# AltiumSTM32_Schematic.net
KiCad netlist of a schematic drawn in Altium Designer
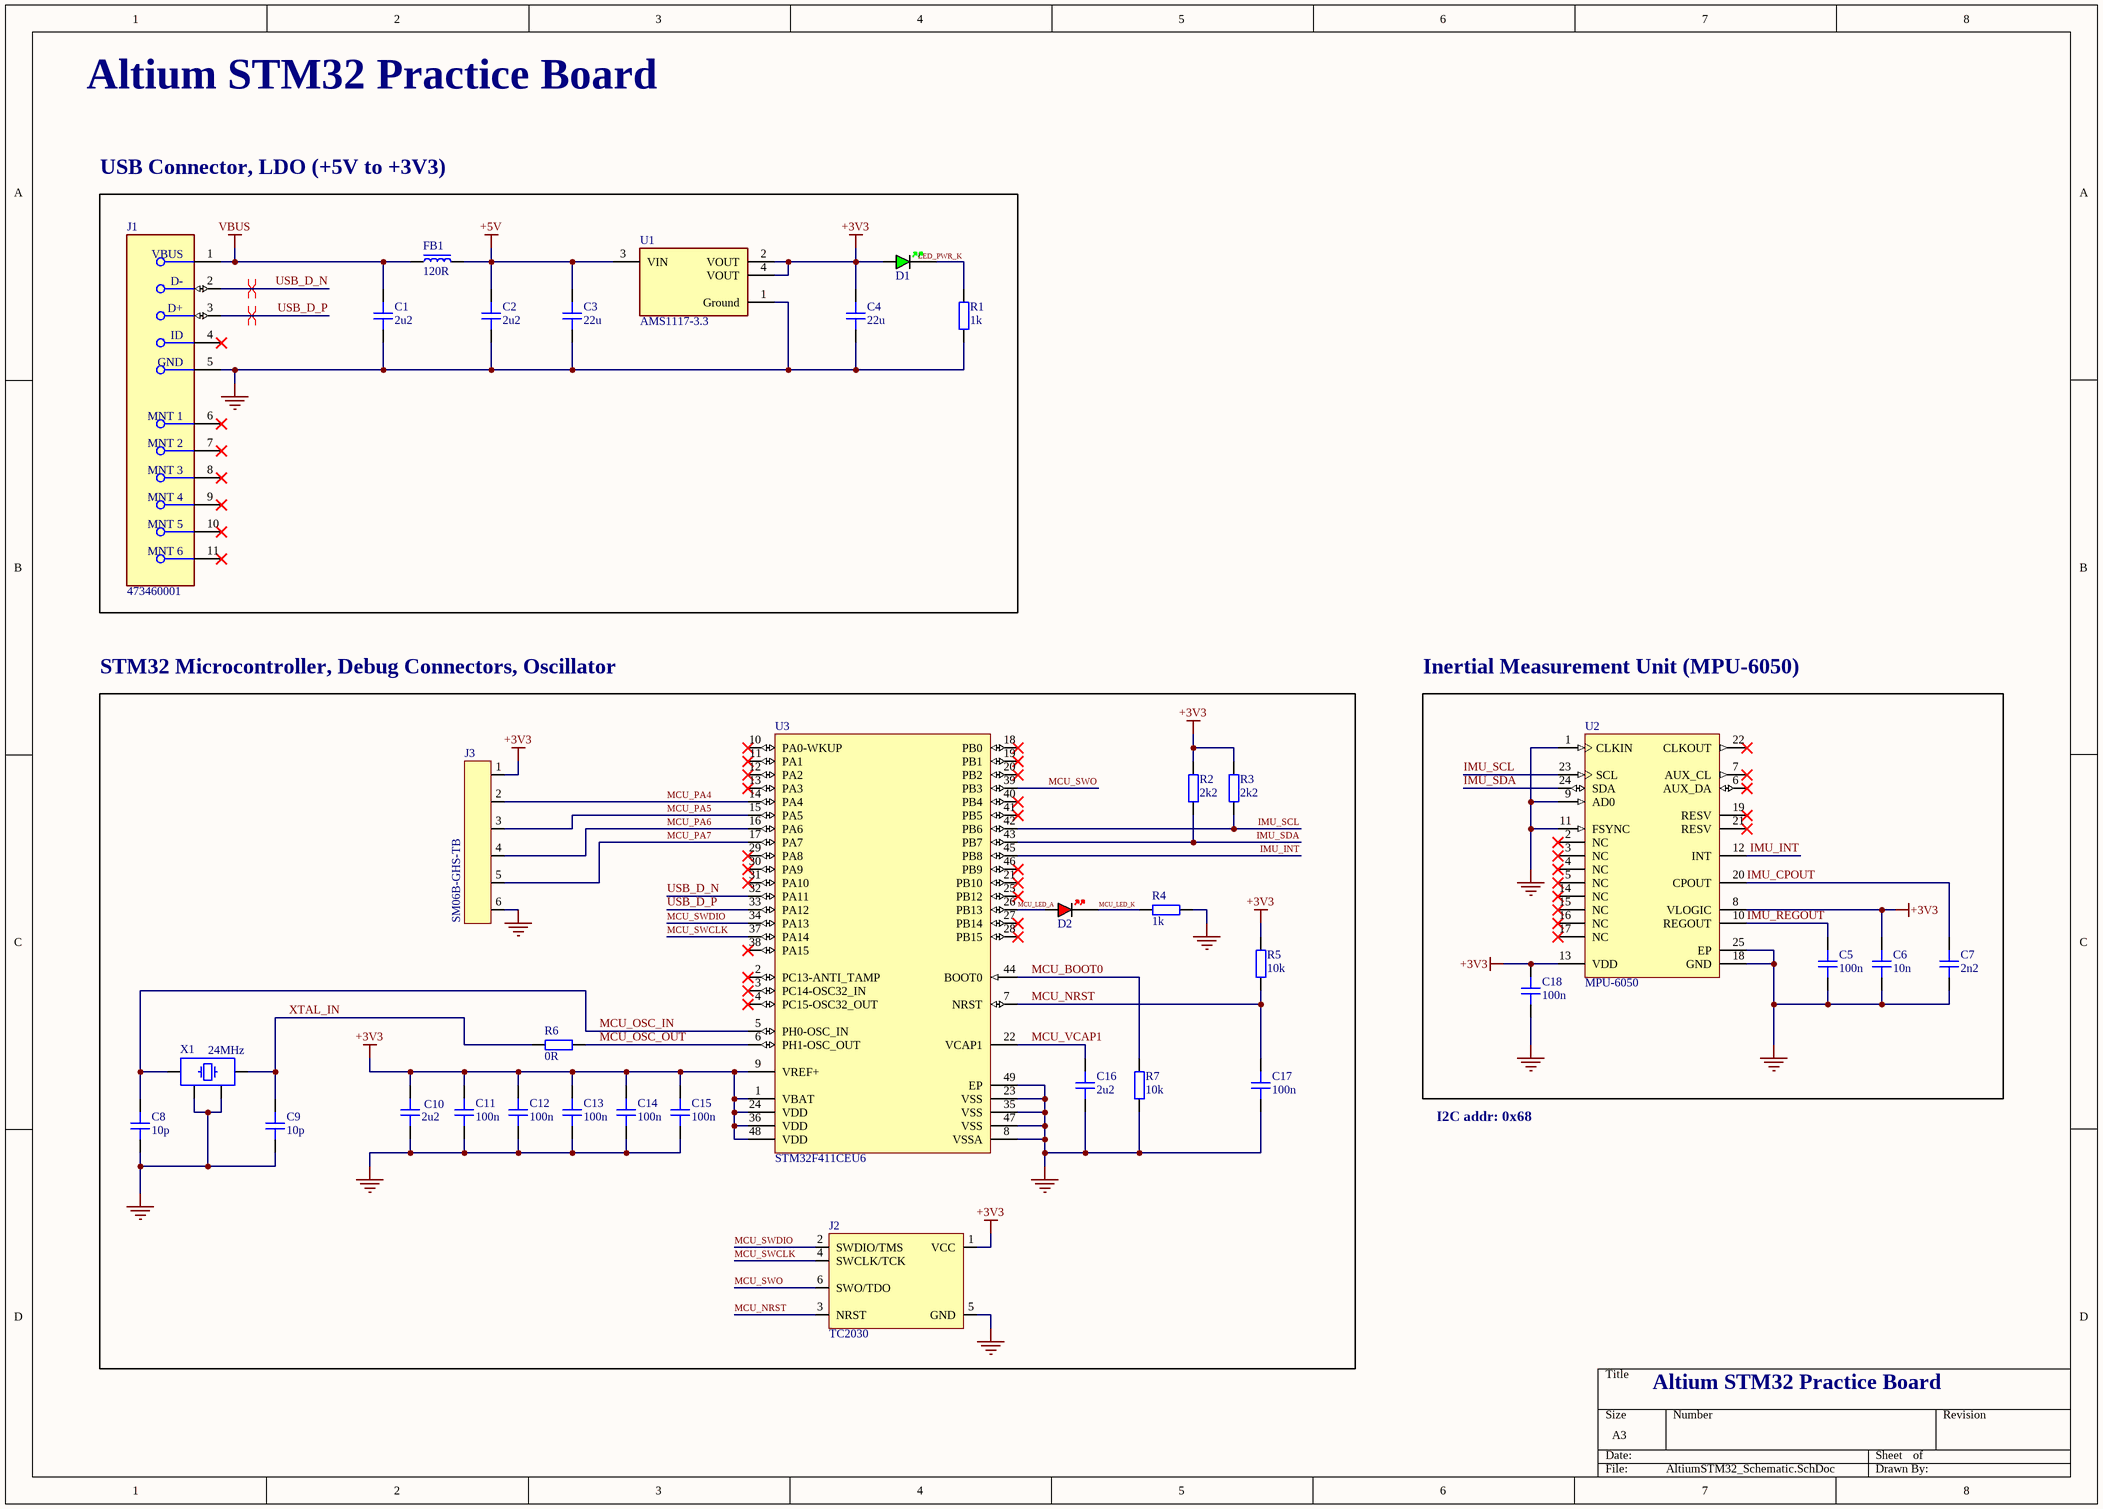
[diagram p0: AltiumSTM32_Schematic.SchDoc]

(export (version "E")
  (design (tool "Eeschema 10.0.6"))
  (components
    (comp (ref "C1")
      (value "2u2")
      (footprint "CAP_0603")
      (description "Capacitor SMD 0603")
      (libsource (lib "Schematic-Lib-PhilsLab") (part "CAP_0603"))
    )
    (comp (ref "C2")
      (value "2u2")
      (footprint "CAP_0603")
      (description "Capacitor SMD 0603")
      (libsource (lib "Schematic-Lib-PhilsLab") (part "CAP_0603"))
    )
    (comp (ref "C3")
      (value "22u")
      (footprint "CAP_0805")
      (description "Capacitor SMD 0805")
      (libsource (lib "Schematic-Lib-PhilsLab") (part "CAP_0805"))
    )
    (comp (ref "C4")
      (value "22u")
      (footprint "CAP_0805")
      (description "Capacitor SMD 0805")
      (libsource (lib "Schematic-Lib-PhilsLab") (part "CAP_0805"))
    )
    (comp (ref "C5")
      (value "100n")
      (footprint "CAP_0402")
      (description "Capacitor SMD 0402")
      (libsource (lib "Schematic-Lib-PhilsLab") (part "CAP_0402"))
    )
    (comp (ref "C6")
      (value "10n")
      (footprint "CAP_0402")
      (description "Capacitor SMD 0402")
      (libsource (lib "Schematic-Lib-PhilsLab") (part "CAP_0402"))
    )
    (comp (ref "C7")
      (value "2n2")
      (footprint "CAP_0402")
      (description "Capacitor SMD 0402")
      (libsource (lib "Schematic-Lib-PhilsLab") (part "CAP_0402"))
    )
    (comp (ref "C8")
      (value "10p")
      (footprint "CAP_0402")
      (description "Capacitor SMD 0402")
      (libsource (lib "Schematic-Lib-PhilsLab") (part "CAP_0402"))
    )
    (comp (ref "C9")
      (value "10p")
      (footprint "CAP_0402")
      (description "Capacitor SMD 0402")
      (libsource (lib "Schematic-Lib-PhilsLab") (part "CAP_0402"))
    )
    (comp (ref "C10")
      (value "2u2")
      (footprint "CAP_0603")
      (description "Capacitor SMD 0603")
      (libsource (lib "Schematic-Lib-PhilsLab") (part "CAP_0603"))
    )
    (comp (ref "C11")
      (value "100n")
      (footprint "CAP_0402")
      (description "Capacitor SMD 0402")
      (libsource (lib "Schematic-Lib-PhilsLab") (part "CAP_0402"))
    )
    (comp (ref "C12")
      (value "100n")
      (footprint "CAP_0402")
      (description "Capacitor SMD 0402")
      (libsource (lib "Schematic-Lib-PhilsLab") (part "CAP_0402"))
    )
    (comp (ref "C13")
      (value "100n")
      (footprint "CAP_0402")
      (description "Capacitor SMD 0402")
      (libsource (lib "Schematic-Lib-PhilsLab") (part "CAP_0402"))
    )
    (comp (ref "C14")
      (value "100n")
      (footprint "CAP_0402")
      (description "Capacitor SMD 0402")
      (libsource (lib "Schematic-Lib-PhilsLab") (part "CAP_0402"))
    )
    (comp (ref "C15")
      (value "100n")
      (footprint "CAP_0402")
      (description "Capacitor SMD 0402")
      (libsource (lib "Schematic-Lib-PhilsLab") (part "CAP_0402"))
    )
    (comp (ref "C16")
      (value "2u2")
      (footprint "CAP_0603")
      (description "Capacitor SMD 0603")
      (libsource (lib "Schematic-Lib-PhilsLab") (part "CAP_0603"))
    )
    (comp (ref "C17")
      (value "100n")
      (footprint "CAP_0402")
      (description "Capacitor SMD 0402")
      (libsource (lib "Schematic-Lib-PhilsLab") (part "CAP_0402"))
    )
    (comp (ref "C18")
      (value "100n")
      (footprint "CAP_0402")
      (description "Capacitor SMD 0402")
      (libsource (lib "Schematic-Lib-PhilsLab") (part "CAP_0402"))
    )
    (comp (ref "D1")
      (value "GREEN")
      (footprint "LED_0402_GREEN")
      (description "LED 0402 GREEN SMD")
      (libsource (lib "Schematic-Lib-PhilsLab") (part "LED_0402_GREEN"))
    )
    (comp (ref "D2")
      (value "RED")
      (footprint "LED_0402_RED")
      (description "LED 0402 RED SMD")
      (libsource (lib "Schematic-Lib-PhilsLab") (part "LED_0402_RED"))
    )
    (comp (ref "FB1")
      (value "120R")
      (footprint "FB_0603")
      (description "Ferrite Bead SMD 0603")
      (libsource (lib "Schematic-Lib-PhilsLab") (part "FB_0603"))
    )
    (comp (ref "J1")
      (value "473460001")
      (footprint "FP-473460001-MFG")
      (description "CONN RCPT USB2.0 MICRO B SMD R/A")
      (fields
        (field (name "OCTOPART") "https://octopart.com/47346-0001-molex-7164928")
        (field (name "MANUFACTURER") "Molex")
      )
      (libsource (lib "Altium Content Vault") (part "53ae1f1d9b557310b43ca686e5bb76a"))
    )
    (comp (ref "J2")
      (value "TC2030")
      (footprint "TC2030-FP")
      (description "Tag-Connect No-Solder SWD Debug Connector DO NOT PLACE")
      (fields (field (name "MANUFACTURER") "Tag-Connect"))
      (libsource (lib "Schematic-Lib-PhilsLab") (part "TC2030"))
    )
    (comp (ref "J3")
      (value "SM06B-GHS-TB")
      (footprint "SM06B-GHS-TB")
      (description "Header Connector 6 Position 1.25MM Pitch SMD Horizontal JST GH")
      (fields (field (name "MANUFACTURER") "JST"))
      (libsource (lib "Schematic-Lib-PhilsLab") (part "SM06B-GHS-TB"))
    )
    (comp (ref "R1")
      (value "1k")
      (footprint "RES_0402")
      (description "Resistor SMD 0402")
      (libsource (lib "Schematic-Lib-PhilsLab") (part "RES_0402"))
    )
    (comp (ref "R2")
      (value "2k2")
      (footprint "RES_0402")
      (description "Resistor SMD 0402")
      (libsource (lib "Schematic-Lib-PhilsLab") (part "RES_0402"))
    )
    (comp (ref "R3")
      (value "2k2")
      (footprint "RES_0402")
      (description "Resistor SMD 0402")
      (libsource (lib "Schematic-Lib-PhilsLab") (part "RES_0402"))
    )
    (comp (ref "R4")
      (value "1k")
      (footprint "RES_0402")
      (description "Resistor SMD 0402")
      (libsource (lib "Schematic-Lib-PhilsLab") (part "RES_0402"))
    )
    (comp (ref "R5")
      (value "10k")
      (footprint "RES_0402")
      (description "Resistor SMD 0402")
      (libsource (lib "Schematic-Lib-PhilsLab") (part "RES_0402"))
    )
    (comp (ref "R6")
      (value "0R")
      (footprint "RES_0402")
      (description "Resistor SMD 0402")
      (libsource (lib "Schematic-Lib-PhilsLab") (part "RES_0402"))
    )
    (comp (ref "R7")
      (value "10k")
      (footprint "RES_0402")
      (description "Resistor SMD 0402")
      (libsource (lib "Schematic-Lib-PhilsLab") (part "RES_0402"))
    )
    (comp (ref "U1")
      (value "AMS1117-3.3")
      (footprint "FP-AMS1117-IPC_C")
      (description "LDO Voltage Regulators 1A, 3.3V")
      (fields
        (field (name "OCTOPART") "https://octopart.com/ams1117-3.3-advanced+monolithic+systems-25899300")
        (field (name "MANUFACTURER") "Advanced Monolithic Systems")
      )
      (libsource (lib "Altium Content Vault") (part "8bdbb5f8e77002000e30dd2845d0354"))
    )
    (comp (ref "U2")
      (value "MPU-6050")
      (footprint "IS-QFN-24_V")
      (fields (field (name "MANUFACTURER") "InvenSense"))
      (libsource (lib "Altium Content Vault") (part "IS-MPU-6050-QFN-24"))
    )
    (comp (ref "U3")
      (value "STM32F411CEU6")
      (footprint "STM-UFQFPN48_L")
      (libsource (lib "Altium Content Vault") (part "MC-ARM-STM32F411-UFQFPN48"))
    )
    (comp (ref "X1")
      (value "24MHz")
      (footprint "XTAL_3225")
      (description "Crystal SMD 24MHz 10PPM 7pF 3225")
      (fields
        (field (name "MANUFACTURER") "Epson")
        (field (name "MANUFACTURER PART NUMBER") "TSX-3225 24.0000MF15X-AC")
      )
      (libsource (lib "Schematic-Lib-PhilsLab") (part "TSX-3225_24.0000MF15X-AC"))
    )
  )
  (nets
    (net (code "1") (name "+3V3") (class "Default")
      (node (ref "C10") (pin "2") (pinfunction "2_2") (pintype "passive"))
      (node (ref "C11") (pin "2") (pinfunction "2_2") (pintype "passive"))
      (node (ref "C12") (pin "2") (pinfunction "2_2") (pintype "passive"))
      (node (ref "C13") (pin "2") (pinfunction "2_2") (pintype "passive"))
      (node (ref "C14") (pin "2") (pinfunction "2_2") (pintype "passive"))
      (node (ref "C15") (pin "2") (pinfunction "2_2") (pintype "passive"))
      (node (ref "C18") (pin "1") (pinfunction "1_1") (pintype "passive"))
      (node (ref "C4") (pin "2") (pinfunction "2_2") (pintype "passive"))
      (node (ref "C6") (pin "1") (pinfunction "1_1") (pintype "passive"))
      (node (ref "D1") (pin "A") (pinfunction "A_A") (pintype "passive"))
      (node (ref "J2") (pin "1") (pinfunction "VCC_1") (pintype "passive"))
      (node (ref "J3") (pin "1") (pinfunction "1_1") (pintype "passive"))
      (node (ref "R2") (pin "2") (pinfunction "2_2") (pintype "passive"))
      (node (ref "R3") (pin "2") (pinfunction "2_2") (pintype "passive"))
      (node (ref "R5") (pin "2") (pinfunction "2_2") (pintype "passive"))
      (node (ref "U1") (pin "2") (pinfunction "VOUT_2") (pintype "passive"))
      (node (ref "U1") (pin "4") (pinfunction "VOUT_4") (pintype "passive"))
      (node (ref "U2") (pin "13") (pinfunction "VDD_13") (pintype "power_in"))
      (node (ref "U2") (pin "8") (pinfunction "VLOGIC_8") (pintype "power_in"))
      (node (ref "U3") (pin "1") (pinfunction "VBAT_1") (pintype "power_in"))
      (node (ref "U3") (pin "24") (pinfunction "VDD_24") (pintype "power_in"))
      (node (ref "U3") (pin "36") (pinfunction "VDD_36") (pintype "power_in"))
      (node (ref "U3") (pin "48") (pinfunction "VDD_48") (pintype "power_in"))
      (node (ref "U3") (pin "9") (pinfunction "VREF+_9") (pintype "power_in"))
    )
    (net (code "2") (name "+5V") (class "Default")
      (node (ref "C2") (pin "2") (pinfunction "2_2") (pintype "passive"))
      (node (ref "C3") (pin "2") (pinfunction "2_2") (pintype "passive"))
      (node (ref "FB1") (pin "2") (pinfunction "2_2") (pintype "passive"))
      (node (ref "U1") (pin "3") (pinfunction "VIN_3") (pintype "power_in"))
    )
    (net (code "3") (name "/IMU_CPOUT") (class "Default")
      (node (ref "C7") (pin "1") (pinfunction "1_1") (pintype "passive"))
      (node (ref "U2") (pin "20") (pinfunction "CPOUT_20") (pintype "passive"))
    )
    (net (code "4") (name "/IMU_INT") (class "Default")
      (node (ref "U2") (pin "12") (pinfunction "INT_12") (pintype "open_collector"))
      (node (ref "U3") (pin "45") (pinfunction "PB8_45") (pintype "bidirectional"))
    )
    (net (code "5") (name "/IMU_REGOUT") (class "Default")
      (node (ref "C5") (pin "1") (pinfunction "1_1") (pintype "passive"))
      (node (ref "U2") (pin "10") (pinfunction "REGOUT_10") (pintype "passive"))
    )
    (net (code "6") (name "/IMU_SCL") (class "Default")
      (node (ref "R3") (pin "1") (pinfunction "1_1") (pintype "passive"))
      (node (ref "U2") (pin "23") (pinfunction "SCL_23") (pintype "input"))
      (node (ref "U3") (pin "42") (pinfunction "PB6_42") (pintype "bidirectional"))
    )
    (net (code "7") (name "/IMU_SDA") (class "Default")
      (node (ref "R2") (pin "1") (pinfunction "1_1") (pintype "passive"))
      (node (ref "U2") (pin "24") (pinfunction "SDA_24") (pintype "bidirectional"))
      (node (ref "U3") (pin "43") (pinfunction "PB7_43") (pintype "bidirectional"))
    )
    (net (code "8") (name "/LED_PWR_K") (class "Default")
      (node (ref "D1") (pin "K") (pinfunction "K_K") (pintype "passive"))
      (node (ref "R1") (pin "2") (pinfunction "2_2") (pintype "passive"))
    )
    (net (code "9") (name "/MCU_BOOT0") (class "Default")
      (node (ref "R7") (pin "2") (pinfunction "2_2") (pintype "passive"))
      (node (ref "U3") (pin "44") (pinfunction "BOOT0_44") (pintype "input"))
    )
    (net (code "10") (name "/MCU_LED_A") (class "Default")
      (node (ref "D2") (pin "A") (pinfunction "A_A") (pintype "passive"))
      (node (ref "U3") (pin "26") (pinfunction "PB13_26") (pintype "bidirectional"))
    )
    (net (code "11") (name "/MCU_LED_K") (class "Default")
      (node (ref "D2") (pin "K") (pinfunction "K_K") (pintype "passive"))
      (node (ref "R4") (pin "2") (pinfunction "2_2") (pintype "passive"))
    )
    (net (code "12") (name "/MCU_NRST") (class "Default")
      (node (ref "C17") (pin "2") (pinfunction "2_2") (pintype "passive"))
      (node (ref "J2") (pin "3") (pinfunction "NRST_3") (pintype "passive"))
      (node (ref "R5") (pin "1") (pinfunction "1_1") (pintype "passive"))
      (node (ref "U3") (pin "7") (pinfunction "NRST_7") (pintype "bidirectional"))
    )
    (net (code "13") (name "/MCU_OSC_IN") (class "Default")
      (node (ref "C8") (pin "2") (pinfunction "2_2") (pintype "passive"))
      (node (ref "U3") (pin "5") (pinfunction "PH0-OSC_IN_5") (pintype "bidirectional"))
      (node (ref "X1") (pin "1") (pinfunction "1_1") (pintype "passive"))
    )
    (net (code "14") (name "/MCU_OSC_OUT") (class "Default")
      (node (ref "R6") (pin "2") (pinfunction "2_2") (pintype "passive"))
      (node (ref "U3") (pin "6") (pinfunction "PH1-OSC_OUT_6") (pintype "bidirectional"))
    )
    (net (code "15") (name "/MCU_PA4") (class "Default")
      (node (ref "J3") (pin "2") (pinfunction "2_2") (pintype "passive"))
      (node (ref "U3") (pin "14") (pinfunction "PA4_14") (pintype "bidirectional"))
    )
    (net (code "16") (name "/MCU_PA5") (class "Default")
      (node (ref "J3") (pin "3") (pinfunction "3_3") (pintype "passive"))
      (node (ref "U3") (pin "15") (pinfunction "PA5_15") (pintype "bidirectional"))
    )
    (net (code "17") (name "/MCU_PA6") (class "Default")
      (node (ref "J3") (pin "4") (pinfunction "4_4") (pintype "passive"))
      (node (ref "U3") (pin "16") (pinfunction "PA6_16") (pintype "bidirectional"))
    )
    (net (code "18") (name "/MCU_PA7") (class "Default")
      (node (ref "J3") (pin "5") (pinfunction "5_5") (pintype "passive"))
      (node (ref "U3") (pin "17") (pinfunction "PA7_17") (pintype "bidirectional"))
    )
    (net (code "19") (name "/MCU_SWCLK") (class "Default")
      (node (ref "J2") (pin "4") (pinfunction "SWCLK/TCK_4") (pintype "passive"))
      (node (ref "U3") (pin "37") (pinfunction "PA14_37") (pintype "bidirectional"))
    )
    (net (code "20") (name "/MCU_SWDIO") (class "Default")
      (node (ref "J2") (pin "2") (pinfunction "SWDIO/TMS_2") (pintype "passive"))
      (node (ref "U3") (pin "34") (pinfunction "PA13_34") (pintype "bidirectional"))
    )
    (net (code "21") (name "/MCU_SWO") (class "Default")
      (node (ref "J2") (pin "6") (pinfunction "SWO/TDO_6") (pintype "passive"))
      (node (ref "U3") (pin "39") (pinfunction "PB3_39") (pintype "bidirectional"))
    )
    (net (code "22") (name "/MCU_VCAP1") (class "Default")
      (node (ref "C16") (pin "2") (pinfunction "2_2") (pintype "passive"))
      (node (ref "U3") (pin "22") (pinfunction "VCAP1_22") (pintype "passive"))
    )
    (net (code "23") (name "/USB_D_N") (class "Default")
      (node (ref "J1") (pin "2") (pinfunction "D-_2") (pintype "bidirectional"))
      (node (ref "U3") (pin "32") (pinfunction "PA11_32") (pintype "bidirectional"))
    )
    (net (code "24") (name "/USB_D_P") (class "Default")
      (node (ref "J1") (pin "3") (pinfunction "D+_3") (pintype "bidirectional"))
      (node (ref "U3") (pin "33") (pinfunction "PA12_33") (pintype "bidirectional"))
    )
    (net (code "25") (name "/XTAL_IN") (class "Default")
      (node (ref "C9") (pin "2") (pinfunction "2_2") (pintype "passive"))
      (node (ref "R6") (pin "1") (pinfunction "1_1") (pintype "passive"))
      (node (ref "X1") (pin "3") (pinfunction "3_3") (pintype "passive"))
    )
    (net (code "26") (name "GND") (class "Default")
      (node (ref "C1") (pin "1") (pinfunction "1_1") (pintype "passive"))
      (node (ref "C10") (pin "1") (pinfunction "1_1") (pintype "passive"))
      (node (ref "C11") (pin "1") (pinfunction "1_1") (pintype "passive"))
      (node (ref "C12") (pin "1") (pinfunction "1_1") (pintype "passive"))
      (node (ref "C13") (pin "1") (pinfunction "1_1") (pintype "passive"))
      (node (ref "C14") (pin "1") (pinfunction "1_1") (pintype "passive"))
      (node (ref "C15") (pin "1") (pinfunction "1_1") (pintype "passive"))
      (node (ref "C16") (pin "1") (pinfunction "1_1") (pintype "passive"))
      (node (ref "C17") (pin "1") (pinfunction "1_1") (pintype "passive"))
      (node (ref "C18") (pin "2") (pinfunction "2_2") (pintype "passive"))
      (node (ref "C2") (pin "1") (pinfunction "1_1") (pintype "passive"))
      (node (ref "C3") (pin "1") (pinfunction "1_1") (pintype "passive"))
      (node (ref "C4") (pin "1") (pinfunction "1_1") (pintype "passive"))
      (node (ref "C5") (pin "2") (pinfunction "2_2") (pintype "passive"))
      (node (ref "C6") (pin "2") (pinfunction "2_2") (pintype "passive"))
      (node (ref "C7") (pin "2") (pinfunction "2_2") (pintype "passive"))
      (node (ref "C8") (pin "1") (pinfunction "1_1") (pintype "passive"))
      (node (ref "C9") (pin "1") (pinfunction "1_1") (pintype "passive"))
      (node (ref "J1") (pin "5") (pinfunction "GND_5") (pintype "power_in"))
      (node (ref "J2") (pin "5") (pinfunction "GND_5") (pintype "passive"))
      (node (ref "J3") (pin "6") (pinfunction "6_6") (pintype "passive"))
      (node (ref "R1") (pin "1") (pinfunction "1_1") (pintype "passive"))
      (node (ref "R4") (pin "1") (pinfunction "1_1") (pintype "passive"))
      (node (ref "R7") (pin "1") (pinfunction "1_1") (pintype "passive"))
      (node (ref "U1") (pin "1") (pinfunction "Ground_1") (pintype "power_in"))
      (node (ref "U2") (pin "1") (pinfunction "CLKIN_1") (pintype "input"))
      (node (ref "U2") (pin "11") (pinfunction "FSYNC_11") (pintype "input"))
      (node (ref "U2") (pin "18") (pinfunction "GND_18") (pintype "power_in"))
      (node (ref "U2") (pin "25") (pinfunction "EP_25") (pintype "power_in"))
      (node (ref "U2") (pin "9") (pinfunction "AD0_9") (pintype "input"))
      (node (ref "U3") (pin "23") (pinfunction "VSS_23") (pintype "power_in"))
      (node (ref "U3") (pin "35") (pinfunction "VSS_35") (pintype "power_in"))
      (node (ref "U3") (pin "47") (pinfunction "VSS_47") (pintype "power_in"))
      (node (ref "U3") (pin "49") (pinfunction "EP_49") (pintype "power_in"))
      (node (ref "U3") (pin "8") (pinfunction "VSSA_8") (pintype "power_in"))
      (node (ref "X1") (pin "2") (pinfunction "2_2") (pintype "passive"))
      (node (ref "X1") (pin "4") (pinfunction "4_4") (pintype "passive"))
    )
    (net (code "27") (name "VBUS") (class "Default")
      (node (ref "C1") (pin "2") (pinfunction "2_2") (pintype "passive"))
      (node (ref "FB1") (pin "1") (pinfunction "1_1") (pintype "passive"))
      (node (ref "J1") (pin "1") (pinfunction "VBUS_1") (pintype "power_in"))
    )
    (net (code "28") (name "unconnected-(J1-ID-Pad4)") (class "Default")
      (node (ref "J1") (pin "4") (pinfunction "ID_4") (pintype "passive+no_connect"))
    )
    (net (code "29") (name "unconnected-(J1-MNT_1-Pad6)") (class "Default")
      (node (ref "J1") (pin "6") (pinfunction "MNT_1_6") (pintype "passive+no_connect"))
    )
    (net (code "30") (name "unconnected-(J1-MNT_2-Pad7)") (class "Default")
      (node (ref "J1") (pin "7") (pinfunction "MNT_2_7") (pintype "passive+no_connect"))
    )
    (net (code "31") (name "unconnected-(J1-MNT_3-Pad8)") (class "Default")
      (node (ref "J1") (pin "8") (pinfunction "MNT_3_8") (pintype "passive+no_connect"))
    )
    (net (code "32") (name "unconnected-(J1-MNT_4-Pad9)") (class "Default")
      (node (ref "J1") (pin "9") (pinfunction "MNT_4_9") (pintype "passive+no_connect"))
    )
    (net (code "33") (name "unconnected-(J1-MNT_5-Pad10)") (class "Default")
      (node (ref "J1") (pin "10") (pinfunction "MNT_5_10") (pintype "passive+no_connect"))
    )
    (net (code "34") (name "unconnected-(J1-MNT_6-Pad11)") (class "Default")
      (node (ref "J1") (pin "11") (pinfunction "MNT_6_11") (pintype "passive+no_connect"))
    )
    (net (code "35") (name "unconnected-(U2-AUX_CL-Pad7)") (class "Default")
      (node (ref "U2") (pin "7") (pinfunction "AUX_CL_7") (pintype "output+no_connect"))
    )
    (net (code "36") (name "unconnected-(U2-AUX_DA-Pad6)") (class "Default")
      (node (ref "U2") (pin "6") (pinfunction "AUX_DA_6") (pintype "bidirectional+no_connect"))
    )
    (net (code "37") (name "unconnected-(U2-CLKOUT-Pad22)") (class "Default")
      (node (ref "U2") (pin "22") (pinfunction "CLKOUT_22") (pintype "output+no_connect"))
    )
    (net (code "38") (name "unconnected-(U2-NC-Pad2)") (class "Default")
      (node (ref "U2") (pin "2") (pinfunction "NC_2") (pintype "passive+no_connect"))
    )
    (net (code "39") (name "unconnected-(U2-NC-Pad3)") (class "Default")
      (node (ref "U2") (pin "3") (pinfunction "NC_3") (pintype "passive+no_connect"))
    )
    (net (code "40") (name "unconnected-(U2-NC-Pad4)") (class "Default")
      (node (ref "U2") (pin "4") (pinfunction "NC_4") (pintype "passive+no_connect"))
    )
    (net (code "41") (name "unconnected-(U2-NC-Pad5)") (class "Default")
      (node (ref "U2") (pin "5") (pinfunction "NC_5") (pintype "passive+no_connect"))
    )
    (net (code "42") (name "unconnected-(U2-NC-Pad14)") (class "Default")
      (node (ref "U2") (pin "14") (pinfunction "NC_14") (pintype "passive+no_connect"))
    )
    (net (code "43") (name "unconnected-(U2-NC-Pad15)") (class "Default")
      (node (ref "U2") (pin "15") (pinfunction "NC_15") (pintype "passive+no_connect"))
    )
    (net (code "44") (name "unconnected-(U2-NC-Pad16)") (class "Default")
      (node (ref "U2") (pin "16") (pinfunction "NC_16") (pintype "passive+no_connect"))
    )
    (net (code "45") (name "unconnected-(U2-NC-Pad17)") (class "Default")
      (node (ref "U2") (pin "17") (pinfunction "NC_17") (pintype "passive+no_connect"))
    )
    (net (code "46") (name "unconnected-(U2-RESV-Pad19)") (class "Default")
      (node (ref "U2") (pin "19") (pinfunction "RESV_19") (pintype "passive+no_connect"))
    )
    (net (code "47") (name "unconnected-(U2-RESV-Pad21)") (class "Default")
      (node (ref "U2") (pin "21") (pinfunction "RESV_21") (pintype "passive+no_connect"))
    )
    (net (code "48") (name "unconnected-(U3-PA0-WKUP-Pad10)") (class "Default")
      (node (ref "U3") (pin "10") (pinfunction "PA0-WKUP_10") (pintype "bidirectional+no_connect"))
    )
    (net (code "49") (name "unconnected-(U3-PA1-Pad11)") (class "Default")
      (node (ref "U3") (pin "11") (pinfunction "PA1_11") (pintype "bidirectional+no_connect"))
    )
    (net (code "50") (name "unconnected-(U3-PA2-Pad12)") (class "Default")
      (node (ref "U3") (pin "12") (pinfunction "PA2_12") (pintype "bidirectional+no_connect"))
    )
    (net (code "51") (name "unconnected-(U3-PA3-Pad13)") (class "Default")
      (node (ref "U3") (pin "13") (pinfunction "PA3_13") (pintype "bidirectional+no_connect"))
    )
    (net (code "52") (name "unconnected-(U3-PA8-Pad29)") (class "Default")
      (node (ref "U3") (pin "29") (pinfunction "PA8_29") (pintype "bidirectional+no_connect"))
    )
    (net (code "53") (name "unconnected-(U3-PA9-Pad30)") (class "Default")
      (node (ref "U3") (pin "30") (pinfunction "PA9_30") (pintype "bidirectional+no_connect"))
    )
    (net (code "54") (name "unconnected-(U3-PA10-Pad31)") (class "Default")
      (node (ref "U3") (pin "31") (pinfunction "PA10_31") (pintype "bidirectional+no_connect"))
    )
    (net (code "55") (name "unconnected-(U3-PA15-Pad38)") (class "Default")
      (node (ref "U3") (pin "38") (pinfunction "PA15_38") (pintype "bidirectional+no_connect"))
    )
    (net (code "56") (name "unconnected-(U3-PB0-Pad18)") (class "Default")
      (node (ref "U3") (pin "18") (pinfunction "PB0_18") (pintype "bidirectional+no_connect"))
    )
    (net (code "57") (name "unconnected-(U3-PB1-Pad19)") (class "Default")
      (node (ref "U3") (pin "19") (pinfunction "PB1_19") (pintype "bidirectional+no_connect"))
    )
    (net (code "58") (name "unconnected-(U3-PB2-Pad20)") (class "Default")
      (node (ref "U3") (pin "20") (pinfunction "PB2_20") (pintype "bidirectional+no_connect"))
    )
    (net (code "59") (name "unconnected-(U3-PB4-Pad40)") (class "Default")
      (node (ref "U3") (pin "40") (pinfunction "PB4_40") (pintype "bidirectional+no_connect"))
    )
    (net (code "60") (name "unconnected-(U3-PB5-Pad41)") (class "Default")
      (node (ref "U3") (pin "41") (pinfunction "PB5_41") (pintype "bidirectional+no_connect"))
    )
    (net (code "61") (name "unconnected-(U3-PB9-Pad46)") (class "Default")
      (node (ref "U3") (pin "46") (pinfunction "PB9_46") (pintype "bidirectional+no_connect"))
    )
    (net (code "62") (name "unconnected-(U3-PB10-Pad21)") (class "Default")
      (node (ref "U3") (pin "21") (pinfunction "PB10_21") (pintype "bidirectional+no_connect"))
    )
    (net (code "63") (name "unconnected-(U3-PB12-Pad25)") (class "Default")
      (node (ref "U3") (pin "25") (pinfunction "PB12_25") (pintype "bidirectional+no_connect"))
    )
    (net (code "64") (name "unconnected-(U3-PB14-Pad27)") (class "Default")
      (node (ref "U3") (pin "27") (pinfunction "PB14_27") (pintype "bidirectional+no_connect"))
    )
    (net (code "65") (name "unconnected-(U3-PB15-Pad28)") (class "Default")
      (node (ref "U3") (pin "28") (pinfunction "PB15_28") (pintype "bidirectional+no_connect"))
    )
    (net (code "66") (name "unconnected-(U3-PC13-ANTI_TAMP-Pad2)") (class "Default")
      (node (ref "U3") (pin "2") (pinfunction "PC13-ANTI_TAMP_2") (pintype "bidirectional+no_connect"))
    )
    (net (code "67") (name "unconnected-(U3-PC14-OSC32_IN-Pad3)") (class "Default")
      (node (ref "U3") (pin "3") (pinfunction "PC14-OSC32_IN_3") (pintype "bidirectional+no_connect"))
    )
    (net (code "68") (name "unconnected-(U3-PC15-OSC32_OUT-Pad4)") (class "Default")
      (node (ref "U3") (pin "4") (pinfunction "PC15-OSC32_OUT_4") (pintype "bidirectional+no_connect"))
    )
  )
)
